# SH1_-_HSD.net
KiCad netlist of a schematic drawn in Altium Designer
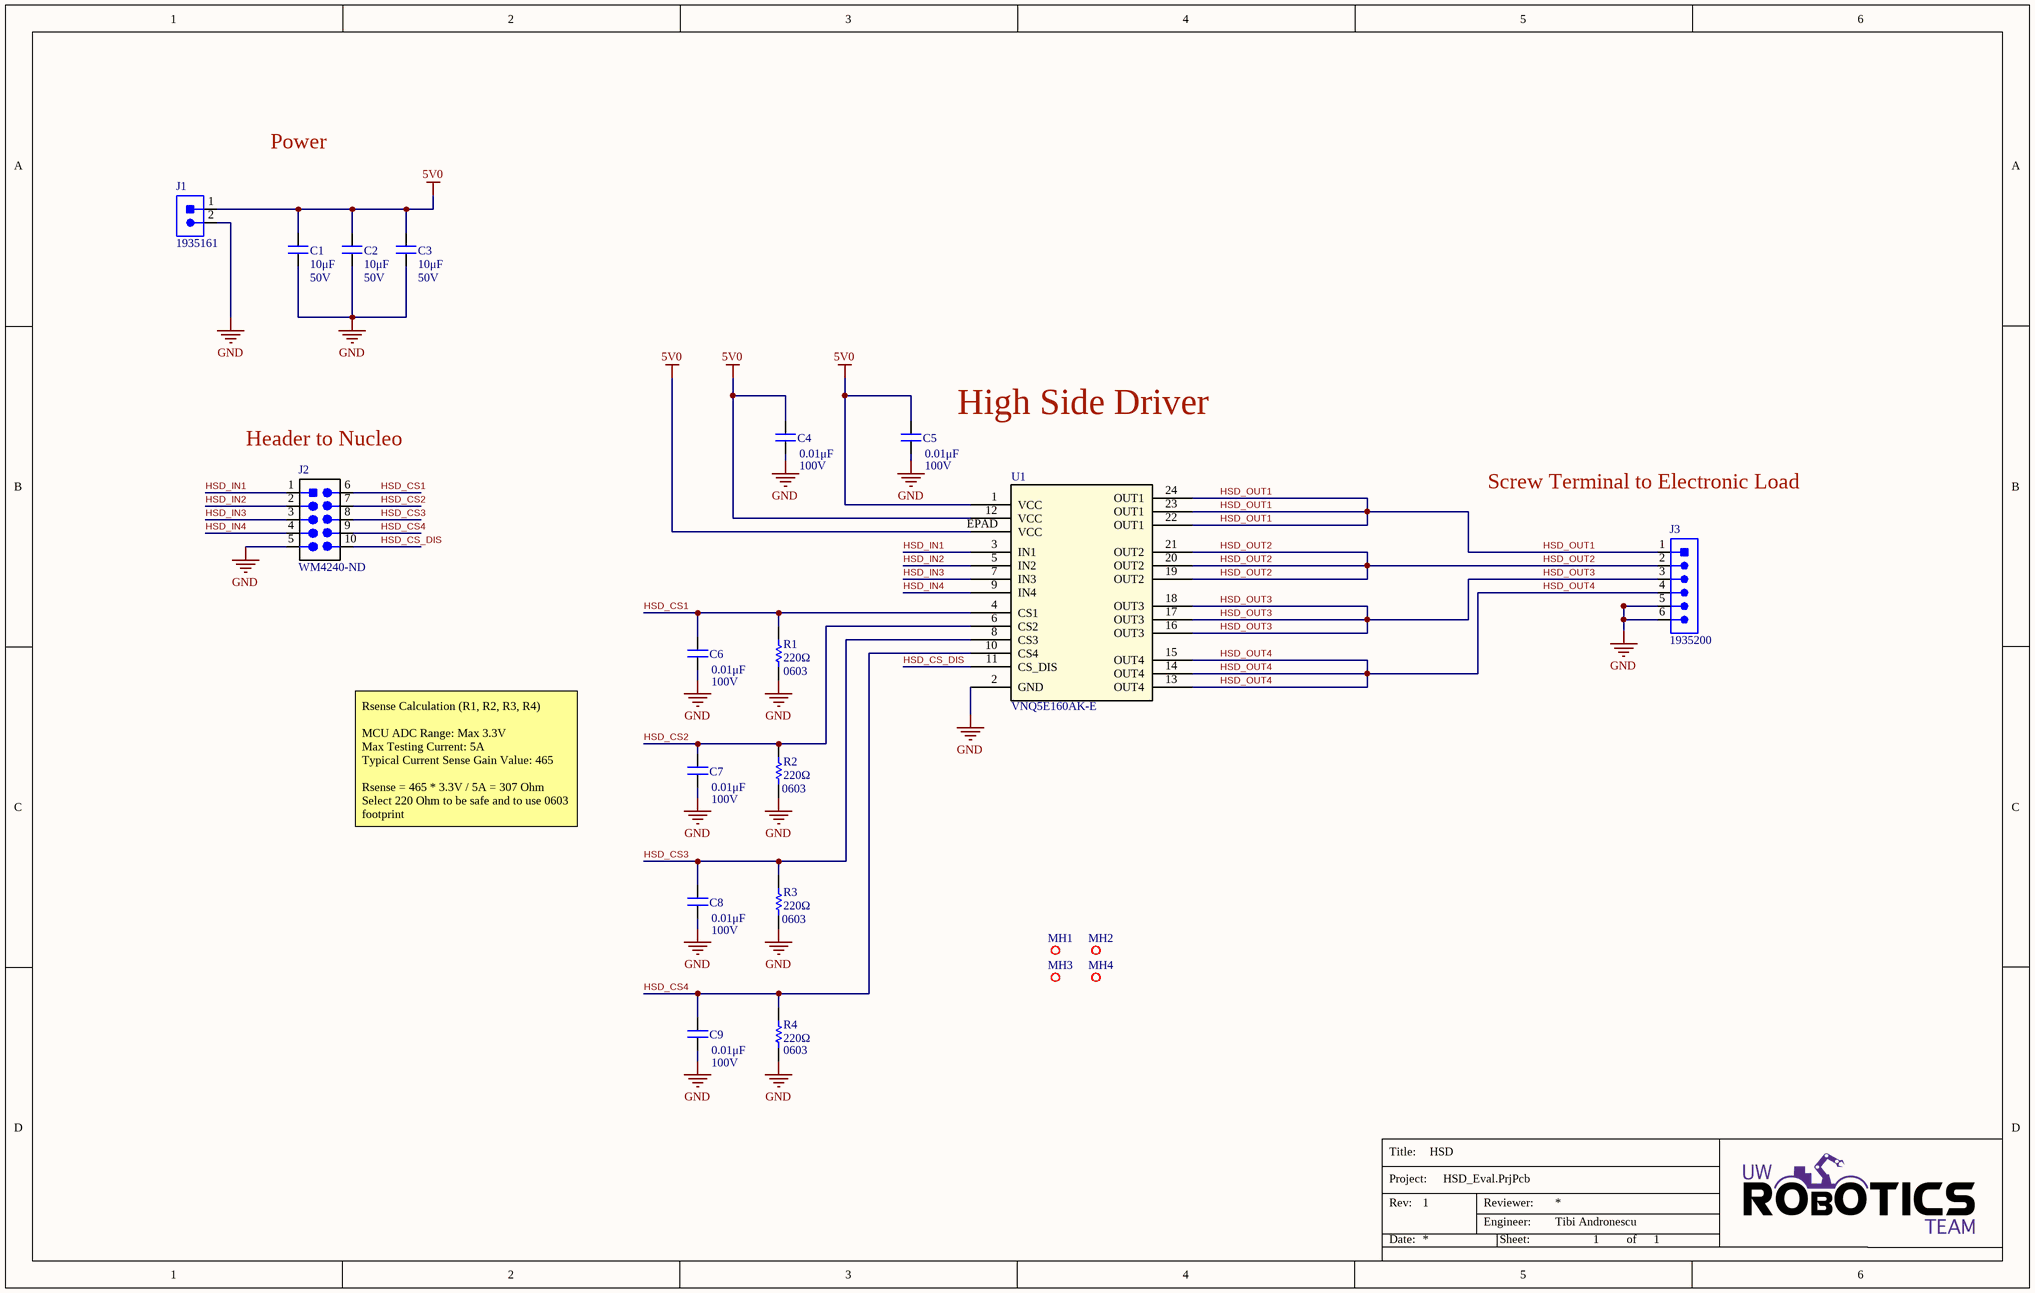
[diagram p0: SH1 - HSD.SchDoc]

(export (version "E")
  (design (tool "Eeschema 10.0.6"))
  (components
    (comp (ref "C1")
      (value "10μF")
      (footprint "CAP1206")
      (description "CAP CER 10UF 50V X5R 1206")
      (fields (field (name "VOLTAGE RATING") "50V") (field (name "Comment") "CAP_10uF_50V_1206"))
      (libsource (lib "UWRT_Schematic_Library_2020") (part "CAP_10uF_50V_1206"))
    )
    (comp (ref "C2")
      (value "10μF")
      (footprint "CAP1206")
      (description "CAP CER 10UF 50V X5R 1206")
      (fields (field (name "VOLTAGE RATING") "50V") (field (name "Comment") "CAP_10uF_50V_1206"))
      (libsource (lib "UWRT_Schematic_Library_2020") (part "CAP_10uF_50V_1206"))
    )
    (comp (ref "C3")
      (value "10μF")
      (footprint "CAP1206")
      (description "CAP CER 10UF 50V X5R 1206")
      (fields (field (name "VOLTAGE RATING") "50V") (field (name "Comment") "CAP_10uF_50V_1206"))
      (libsource (lib "UWRT_Schematic_Library_2020") (part "CAP_10uF_50V_1206"))
    )
    (comp (ref "C4")
      (value "0.01μF")
      (footprint "CAP0603")
      (description "CAP CER 10000PF 100V X7R 0603")
      (fields (field (name "VOLTAGE RATING") "100V") (field (name "Comment") "CAP_0.01uF_100V_0603"))
      (libsource (lib "UWRT_Schematic_Library_2020") (part "CAP_0.01uF_100V_0603"))
    )
    (comp (ref "C5")
      (value "0.01μF")
      (footprint "CAP0603")
      (description "CAP CER 10000PF 100V X7R 0603")
      (fields (field (name "VOLTAGE RATING") "100V") (field (name "Comment") "CAP_0.01uF_100V_0603"))
      (libsource (lib "UWRT_Schematic_Library_2020") (part "CAP_0.01uF_100V_0603"))
    )
    (comp (ref "C6")
      (value "0.01μF")
      (footprint "CAP0603")
      (description "CAP CER 10000PF 100V X7R 0603")
      (fields (field (name "VOLTAGE RATING") "100V") (field (name "Comment") "CAP_0.01uF_100V_0603"))
      (libsource (lib "UWRT_Schematic_Library_2020") (part "CAP_0.01uF_100V_0603"))
    )
    (comp (ref "C7")
      (value "0.01μF")
      (footprint "CAP0603")
      (description "CAP CER 10000PF 100V X7R 0603")
      (fields (field (name "VOLTAGE RATING") "100V") (field (name "Comment") "CAP_0.01uF_100V_0603"))
      (libsource (lib "UWRT_Schematic_Library_2020") (part "CAP_0.01uF_100V_0603"))
    )
    (comp (ref "C8")
      (value "0.01μF")
      (footprint "CAP0603")
      (description "CAP CER 10000PF 100V X7R 0603")
      (fields (field (name "VOLTAGE RATING") "100V") (field (name "Comment") "CAP_0.01uF_100V_0603"))
      (libsource (lib "UWRT_Schematic_Library_2020") (part "CAP_0.01uF_100V_0603"))
    )
    (comp (ref "C9")
      (value "0.01μF")
      (footprint "CAP0603")
      (description "CAP CER 10000PF 100V X7R 0603")
      (fields (field (name "VOLTAGE RATING") "100V") (field (name "Comment") "CAP_0.01uF_100V_0603"))
      (libsource (lib "UWRT_Schematic_Library_2020") (part "CAP_0.01uF_100V_0603"))
    )
    (comp (ref "J1")
      (value "CON_2M_TERM")
      (footprint "1935161")
      (description "TERM BLK 2POS SIDE ENTRY 5MM")
      (fields (field (name "VOLTAGE") "300V") (field (name "MANUFACTURER PART NUMBER 1") "1935161"))
      (libsource (lib "UWRT_Schematic_Library_2020") (part "CON_2M_TERM"))
    )
    (comp (ref "J2")
      (value "HEADER 5x2")
      (footprint "HEADER 2X5")
      (description "CONN HEADER VERT 10POS 2.54MM")
      (fields (field (name "SUPPLIER PART NUMBER 1") "WM4240-ND"))
      (libsource (lib "UWRT_Schematic_Library_2020") (part "HEADER 5x2"))
    )
    (comp (ref "J3")
      (value "CON_6POS_SCREW_TERM")
      (footprint "1935200")
      (description "TERM BLK 6POS SIDE ENTRY 5MM")
      (fields (field (name "MANUFACTURER PART NUMBER 1") "1935200"))
      (libsource (lib "UWRT_Schematic_Library_2020") (part "CON_6POS_SCREW_TERM"))
    )
    (comp (ref "MH1")
      (value "MOUNTING_HOLE_M3")
      (footprint "MOUNTING_HOLE_3mm")
      (libsource (lib "UWRT_Schematic_Library_2020") (part "MOUNTING_HOLE_M3"))
    )
    (comp (ref "MH2")
      (value "MOUNTING_HOLE_M3")
      (footprint "MOUNTING_HOLE_3mm")
      (libsource (lib "UWRT_Schematic_Library_2020") (part "MOUNTING_HOLE_M3"))
    )
    (comp (ref "MH3")
      (value "MOUNTING_HOLE_M3")
      (footprint "MOUNTING_HOLE_3mm")
      (libsource (lib "UWRT_Schematic_Library_2020") (part "MOUNTING_HOLE_M3"))
    )
    (comp (ref "MH4")
      (value "MOUNTING_HOLE_M3")
      (footprint "MOUNTING_HOLE_3mm")
      (libsource (lib "UWRT_Schematic_Library_2020") (part "MOUNTING_HOLE_M3"))
    )
    (comp (ref "R1")
      (value "220Ω")
      (footprint "RESC0603")
      (description "RES 220 OHM 5% 1/10W 0603")
      (fields (field (name "PACKAGE/FOOTPRINT") "0603") (field (name "Comment") "RES_220Ω_0603"))
      (libsource (lib "UWRT_Schematic_Library_2020") (part "RES_220Ω_0603_5%"))
    )
    (comp (ref "R2")
      (value "220Ω")
      (footprint "RESC0603")
      (description "RES 220 OHM 5% 1/10W 0603")
      (fields (field (name "PACKAGE/FOOTPRINT") "0603") (field (name "Comment") "RES_220Ω_0603"))
      (libsource (lib "UWRT_Schematic_Library_2020") (part "RES_220Ω_0603_5%"))
    )
    (comp (ref "R3")
      (value "220Ω")
      (footprint "RESC0603")
      (description "RES 220 OHM 5% 1/10W 0603")
      (fields (field (name "PACKAGE/FOOTPRINT") "0603") (field (name "Comment") "RES_220Ω_0603"))
      (libsource (lib "UWRT_Schematic_Library_2020") (part "RES_220Ω_0603_5%"))
    )
    (comp (ref "R4")
      (value "220Ω")
      (footprint "RESC0603")
      (description "RES 220 OHM 5% 1/10W 0603")
      (fields (field (name "PACKAGE/FOOTPRINT") "0603") (field (name "Comment") "RES_220Ω_0603"))
      (libsource (lib "UWRT_Schematic_Library_2020") (part "RES_220Ω_0603_5%"))
    )
    (comp (ref "U1")
      (value "VNQ5E160AK-E")
      (footprint "PowerSSO-24_STM")
      (description "Power Switch/Driver 1:1 N-Channel 7A PowerSSO-24")
      (fields (field (name "MANUFACTURER PART NUMBER 1") "VNQ5E160AK-E"))
      (libsource (lib "UWRT_Schematic_Library_2020") (part "VNQ5E160AK-E"))
    )
  )
  (nets
    (net (code "1") (name "/HSD_CS1") (class "Default")
      (node (ref "C6") (pin "2") (pinfunction "2_2") (pintype "passive"))
      (node (ref "J2") (pin "6") (pinfunction "GND_6") (pintype "passive"))
      (node (ref "R1") (pin "2") (pinfunction "2_2") (pintype "passive"))
      (node (ref "U1") (pin "4") (pinfunction "CS1_4") (pintype "passive"))
    )
    (net (code "2") (name "/HSD_CS2") (class "Default")
      (node (ref "C7") (pin "2") (pinfunction "2_2") (pintype "passive"))
      (node (ref "J2") (pin "7") (pinfunction "7_7") (pintype "passive"))
      (node (ref "R2") (pin "2") (pinfunction "2_2") (pintype "passive"))
      (node (ref "U1") (pin "6") (pinfunction "CS2_6") (pintype "passive"))
    )
    (net (code "3") (name "/HSD_CS3") (class "Default")
      (node (ref "C8") (pin "2") (pinfunction "2_2") (pintype "passive"))
      (node (ref "J2") (pin "8") (pinfunction "8_8") (pintype "passive"))
      (node (ref "R3") (pin "2") (pinfunction "2_2") (pintype "passive"))
      (node (ref "U1") (pin "8") (pinfunction "CS3_8") (pintype "passive"))
    )
    (net (code "4") (name "/HSD_CS4") (class "Default")
      (node (ref "C9") (pin "2") (pinfunction "2_2") (pintype "passive"))
      (node (ref "J2") (pin "9") (pinfunction "9_9") (pintype "passive"))
      (node (ref "R4") (pin "2") (pinfunction "2_2") (pintype "passive"))
      (node (ref "U1") (pin "10") (pinfunction "CS4_10") (pintype "passive"))
    )
    (net (code "5") (name "/HSD_CS_DIS") (class "Default")
      (node (ref "J2") (pin "10") (pinfunction "10_10") (pintype "passive"))
      (node (ref "U1") (pin "11") (pinfunction "CS_DIS_11") (pintype "passive"))
    )
    (net (code "6") (name "/HSD_IN1") (class "Default")
      (node (ref "J2") (pin "1") (pinfunction "VCC_1") (pintype "passive"))
      (node (ref "U1") (pin "3") (pinfunction "IN1_3") (pintype "passive"))
    )
    (net (code "7") (name "/HSD_IN2") (class "Default")
      (node (ref "J2") (pin "2") (pinfunction "2_2") (pintype "passive"))
      (node (ref "U1") (pin "5") (pinfunction "IN2_5") (pintype "passive"))
    )
    (net (code "8") (name "/HSD_IN3") (class "Default")
      (node (ref "J2") (pin "3") (pinfunction "3_3") (pintype "passive"))
      (node (ref "U1") (pin "7") (pinfunction "IN3_7") (pintype "passive"))
    )
    (net (code "9") (name "/HSD_IN4") (class "Default")
      (node (ref "J2") (pin "4") (pinfunction "4_4") (pintype "passive"))
      (node (ref "U1") (pin "9") (pinfunction "IN4_9") (pintype "passive"))
    )
    (net (code "10") (name "/HSD_OUT1") (class "Default")
      (node (ref "J3") (pin "1") (pinfunction "1_1") (pintype "passive"))
      (node (ref "U1") (pin "22") (pinfunction "OUT1_22") (pintype "passive"))
      (node (ref "U1") (pin "23") (pinfunction "OUT1_23") (pintype "passive"))
      (node (ref "U1") (pin "24") (pinfunction "OUT1_24") (pintype "passive"))
    )
    (net (code "11") (name "/HSD_OUT2") (class "Default")
      (node (ref "J3") (pin "2") (pinfunction "2_2") (pintype "passive"))
      (node (ref "U1") (pin "19") (pinfunction "OUT2_19") (pintype "passive"))
      (node (ref "U1") (pin "20") (pinfunction "OUT2_20") (pintype "passive"))
      (node (ref "U1") (pin "21") (pinfunction "OUT2_21") (pintype "passive"))
    )
    (net (code "12") (name "/HSD_OUT3") (class "Default")
      (node (ref "J3") (pin "3") (pinfunction "3_3") (pintype "passive"))
      (node (ref "U1") (pin "16") (pinfunction "OUT3_16") (pintype "passive"))
      (node (ref "U1") (pin "17") (pinfunction "OUT3_17") (pintype "passive"))
      (node (ref "U1") (pin "18") (pinfunction "OUT3_18") (pintype "passive"))
    )
    (net (code "13") (name "/HSD_OUT4") (class "Default")
      (node (ref "J3") (pin "4") (pinfunction "4_4") (pintype "passive"))
      (node (ref "U1") (pin "13") (pinfunction "OUT4_13") (pintype "passive"))
      (node (ref "U1") (pin "14") (pinfunction "OUT4_14") (pintype "passive"))
      (node (ref "U1") (pin "15") (pinfunction "OUT4_15") (pintype "passive"))
    )
    (net (code "14") (name "5V0") (class "Default")
      (node (ref "C1") (pin "2") (pinfunction "2_2") (pintype "passive"))
      (node (ref "C2") (pin "2") (pinfunction "2_2") (pintype "passive"))
      (node (ref "C3") (pin "2") (pinfunction "2_2") (pintype "passive"))
      (node (ref "C4") (pin "2") (pinfunction "2_2") (pintype "passive"))
      (node (ref "C5") (pin "2") (pinfunction "2_2") (pintype "passive"))
      (node (ref "J1") (pin "1") (pinfunction "1_1") (pintype "passive"))
      (node (ref "U1") (pin "1") (pinfunction "VCC_1") (pintype "power_in"))
      (node (ref "U1") (pin "12") (pinfunction "VCC_12") (pintype "power_in"))
      (node (ref "U1") (pin "EPAD") (pinfunction "VCC_EPAD") (pintype "power_in"))
    )
    (net (code "15") (name "GND") (class "Default")
      (node (ref "C1") (pin "1") (pinfunction "1_1") (pintype "passive"))
      (node (ref "C2") (pin "1") (pinfunction "1_1") (pintype "passive"))
      (node (ref "C3") (pin "1") (pinfunction "1_1") (pintype "passive"))
      (node (ref "C4") (pin "1") (pinfunction "1_1") (pintype "passive"))
      (node (ref "C5") (pin "1") (pinfunction "1_1") (pintype "passive"))
      (node (ref "C6") (pin "1") (pinfunction "1_1") (pintype "passive"))
      (node (ref "C7") (pin "1") (pinfunction "1_1") (pintype "passive"))
      (node (ref "C8") (pin "1") (pinfunction "1_1") (pintype "passive"))
      (node (ref "C9") (pin "1") (pinfunction "1_1") (pintype "passive"))
      (node (ref "J1") (pin "2") (pinfunction "2_2") (pintype "passive"))
      (node (ref "J2") (pin "5") (pinfunction "5_5") (pintype "passive"))
      (node (ref "J3") (pin "5") (pinfunction "5_5") (pintype "passive"))
      (node (ref "J3") (pin "6") (pinfunction "6_6") (pintype "passive"))
      (node (ref "R1") (pin "1") (pinfunction "1_1") (pintype "passive"))
      (node (ref "R2") (pin "1") (pinfunction "1_1") (pintype "passive"))
      (node (ref "R3") (pin "1") (pinfunction "1_1") (pintype "passive"))
      (node (ref "R4") (pin "1") (pinfunction "1_1") (pintype "passive"))
      (node (ref "U1") (pin "2") (pinfunction "GND_2") (pintype "power_in"))
    )
  )
)
